# Becca_Sap_Flow_Power_Board_MOD.net
KiCad netlist of a schematic drawn in EAGLE
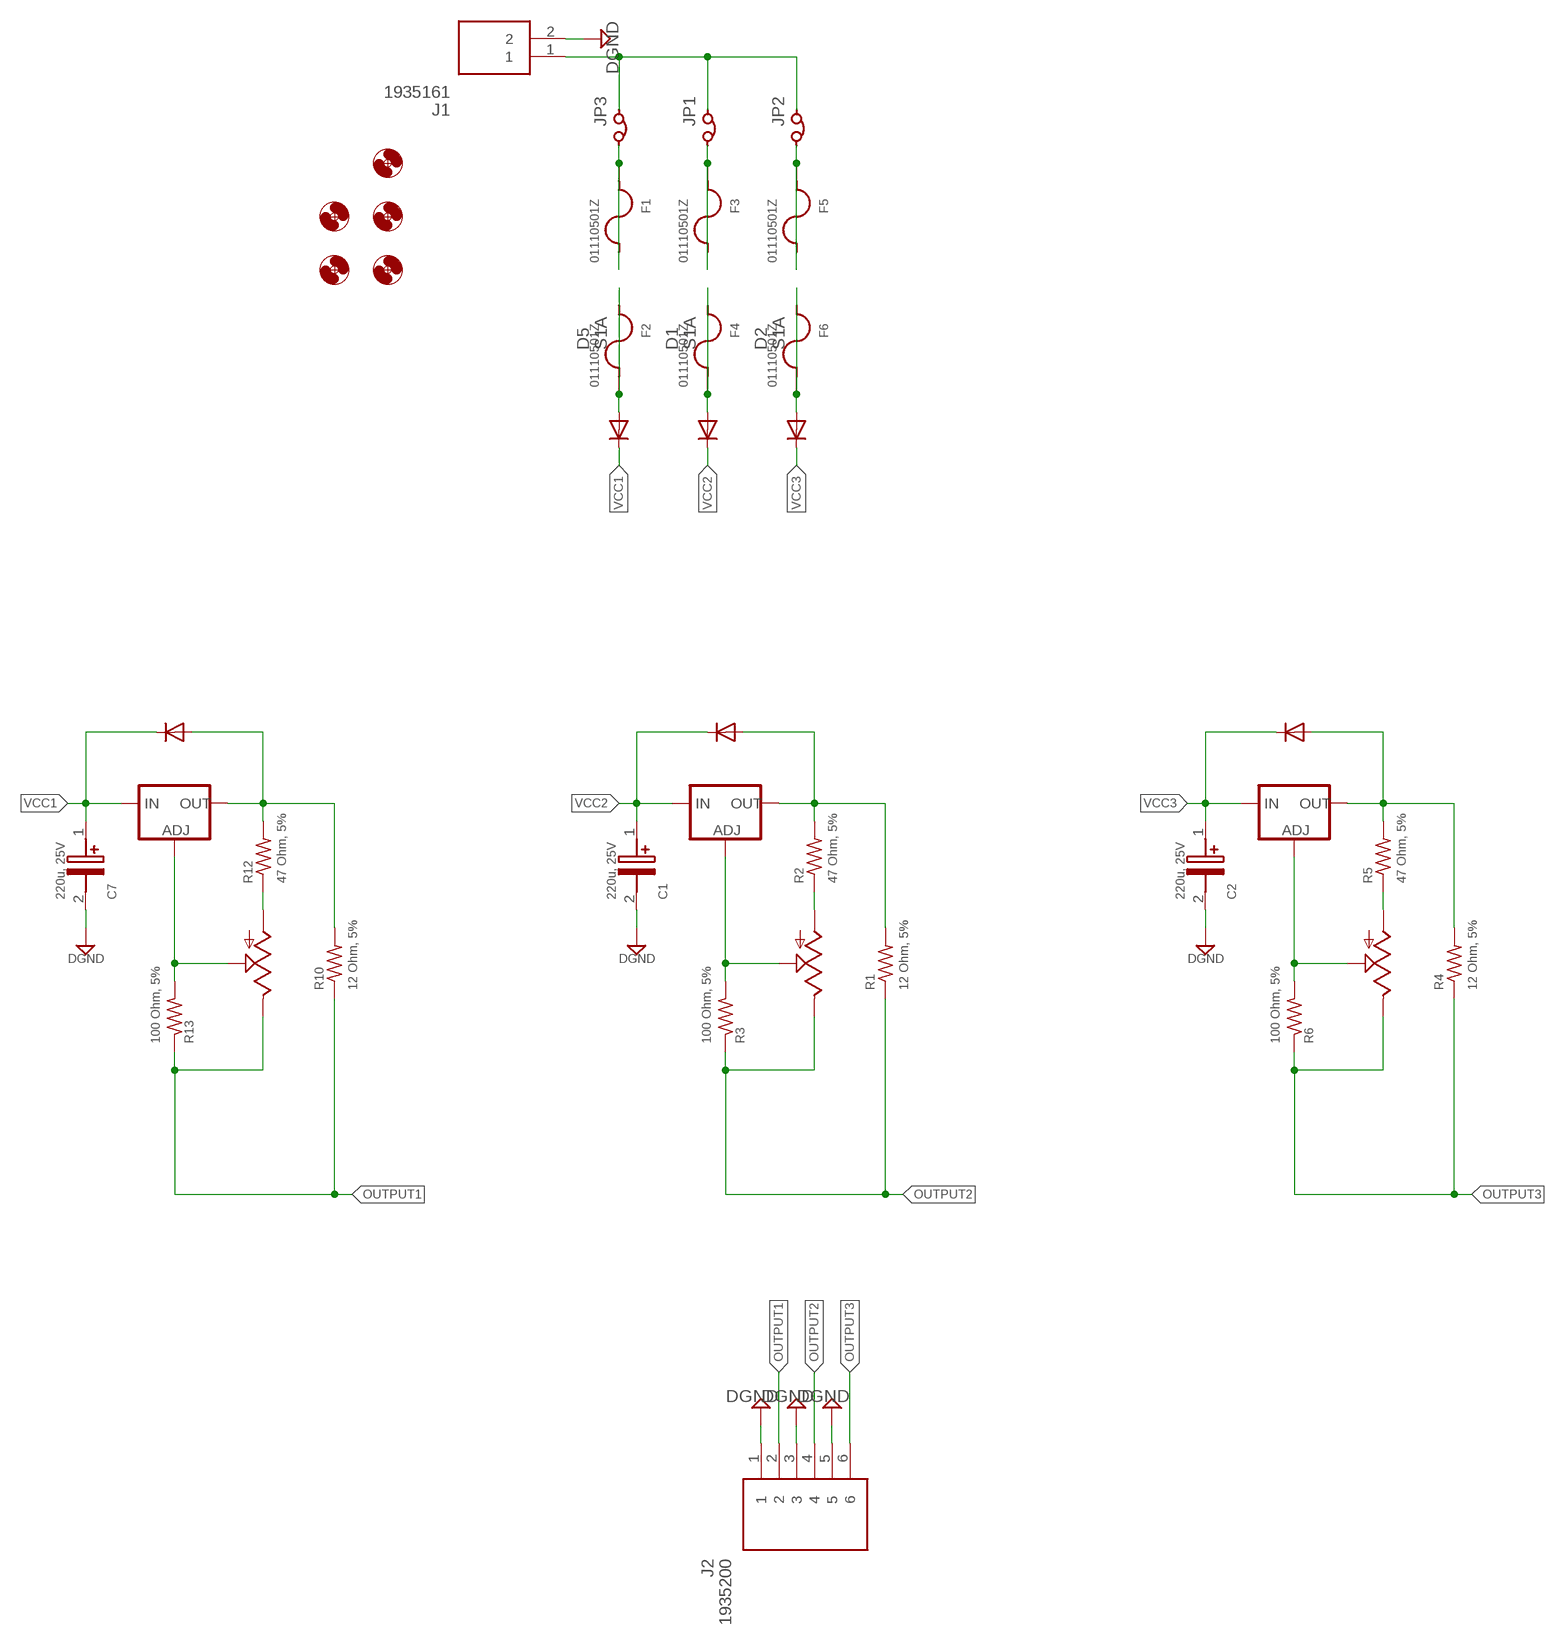
[diagram p0: schematic, sheet 1]

(export (version "E")
  (design (tool "Eeschema 10.0.6"))
  (components
    (comp (ref "C1")
      (value "220u, 25V")
      (footprint "eagle-import:CAPAE830X1080N")
      (fields
        (field (name "MANUFACTURER_PART_NUMBER") "UWT1E221MNL1GS")
        (field (name "MOUSER_PART_NUMBER") "647-UWT1E221MNL1GS")
      )
      (libsource (lib "eagle-import") (part "UWT1E221MNL1GS"))
    )
    (comp (ref "C2")
      (value "220u, 25V")
      (footprint "eagle-import:CAPAE830X1080N")
      (fields
        (field (name "MANUFACTURER_PART_NUMBER") "UWT1E221MNL1GS")
        (field (name "MOUSER_PART_NUMBER") "647-UWT1E221MNL1GS")
      )
      (libsource (lib "eagle-import") (part "UWT1E221MNL1GS"))
    )
    (comp (ref "C7")
      (value "220u, 25V")
      (footprint "eagle-import:CAPAE830X1080N")
      (fields
        (field (name "MANUFACTURER_PART_NUMBER") "UWT1E221MNL1GS")
        (field (name "MOUSER_PART_NUMBER") "647-UWT1E221MNL1GS")
      )
      (libsource (lib "eagle-import") (part "UWT1E221MNL1GS"))
    )
    (comp (ref "D1")
      (value "S1A")
      (footprint "eagle-import:DIOM5027X250N")
      (fields (field (name "MOUSER_PART_NUMBER") "637-S1A"))
      (libsource (lib "eagle-import") (part "S1A"))
    )
    (comp (ref "D2")
      (value "S1A")
      (footprint "eagle-import:DIOM5027X250N")
      (fields (field (name "MOUSER_PART_NUMBER") "637-S1A"))
      (libsource (lib "eagle-import") (part "S1A"))
    )
    (comp (ref "D3")
      (value "S1A")
      (footprint "eagle-import:DIOM5027X250N")
      (fields (field (name "MOUSER_PART_NUMBER") "637-S1A"))
      (libsource (lib "eagle-import") (part "S1A"))
    )
    (comp (ref "D4")
      (value "S1A")
      (footprint "eagle-import:DIOM5027X250N")
      (fields (field (name "MOUSER_PART_NUMBER") "637-S1A"))
      (libsource (lib "eagle-import") (part "S1A"))
    )
    (comp (ref "D5")
      (value "S1A")
      (footprint "eagle-import:DIOM5027X250N")
      (fields (field (name "MOUSER_PART_NUMBER") "637-S1A"))
      (libsource (lib "eagle-import") (part "S1A"))
    )
    (comp (ref "D6")
      (value "S1A")
      (footprint "eagle-import:DIOM5027X250N")
      (fields (field (name "MOUSER_PART_NUMBER") "637-S1A"))
      (libsource (lib "eagle-import") (part "S1A"))
    )
    (comp (ref "F1")
      (value "01110501Z")
      (footprint "eagle-import:01110501Z")
      (fields (field (name "MOUSER_PART_NUMBER") "576-01110501Z"))
      (libsource (lib "eagle-import") (part "01110501Z"))
    )
    (comp (ref "F2")
      (value "01110501Z")
      (footprint "eagle-import:01110501Z")
      (fields (field (name "MOUSER_PART_NUMBER") "576-01110501Z"))
      (libsource (lib "eagle-import") (part "01110501Z"))
    )
    (comp (ref "F3")
      (value "01110501Z")
      (footprint "eagle-import:01110501Z")
      (fields (field (name "MOUSER_PART_NUMBER") "576-01110501Z"))
      (libsource (lib "eagle-import") (part "01110501Z"))
    )
    (comp (ref "F4")
      (value "01110501Z")
      (footprint "eagle-import:01110501Z")
      (fields (field (name "MOUSER_PART_NUMBER") "576-01110501Z"))
      (libsource (lib "eagle-import") (part "01110501Z"))
    )
    (comp (ref "F5")
      (value "01110501Z")
      (footprint "eagle-import:01110501Z")
      (fields (field (name "MOUSER_PART_NUMBER") "576-01110501Z"))
      (libsource (lib "eagle-import") (part "01110501Z"))
    )
    (comp (ref "F6")
      (value "01110501Z")
      (footprint "eagle-import:01110501Z")
      (fields (field (name "MOUSER_PART_NUMBER") "576-01110501Z"))
      (libsource (lib "eagle-import") (part "01110501Z"))
    )
    (comp (ref "J1")
      (value "1935161")
      (footprint "eagle-import:1935161")
      (fields (field (name "MOUSER_PART_NUMBER") "651-1935161"))
      (libsource (lib "eagle-import") (part "1935161"))
    )
    (comp (ref "J2")
      (value "1935200")
      (footprint "eagle-import:1935200")
      (fields (field (name "MOUSER_PART_NUMBER") "651-1935200"))
      (libsource (lib "eagle-import") (part "1935200"))
    )
    (comp (ref "JP1")
      (value "JUMPER")
      (footprint "eagle-import:HDR2X1")
      (libsource (lib "eagle-import") (part "JUMPER"))
    )
    (comp (ref "JP2")
      (value "JUMPER")
      (footprint "eagle-import:HDR2X1")
      (libsource (lib "eagle-import") (part "JUMPER"))
    )
    (comp (ref "JP3")
      (value "JUMPER")
      (footprint "eagle-import:HDR2X1")
      (libsource (lib "eagle-import") (part "JUMPER"))
    )
    (comp (ref "R1")
      (value "12 Ohm, 5%")
      (footprint "eagle-import:R1210")
      (libsource (lib "eagle-import") (part "R-US_R1210"))
    )
    (comp (ref "R2")
      (value "47 Ohm, 5%")
      (footprint "eagle-import:R1210")
      (libsource (lib "eagle-import") (part "R-US_R1210"))
    )
    (comp (ref "R3")
      (value "100 Ohm, 5%")
      (footprint "eagle-import:R1210")
      (libsource (lib "eagle-import") (part "R-US_R1210"))
    )
    (comp (ref "R4")
      (value "12 Ohm, 5%")
      (footprint "eagle-import:R1210")
      (libsource (lib "eagle-import") (part "R-US_R1210"))
    )
    (comp (ref "R5")
      (value "47 Ohm, 5%")
      (footprint "eagle-import:R1210")
      (libsource (lib "eagle-import") (part "R-US_R1210"))
    )
    (comp (ref "R6")
      (value "100 Ohm, 5%")
      (footprint "eagle-import:R1210")
      (libsource (lib "eagle-import") (part "R-US_R1210"))
    )
    (comp (ref "R10")
      (value "12 Ohm, 5%")
      (footprint "eagle-import:R1210")
      (libsource (lib "eagle-import") (part "R-US_R1210"))
    )
    (comp (ref "R12")
      (value "47 Ohm, 5%")
      (footprint "eagle-import:R1210")
      (libsource (lib "eagle-import") (part "R-US_R1210"))
    )
    (comp (ref "R13")
      (value "100 Ohm, 5%")
      (footprint "eagle-import:R1210")
      (libsource (lib "eagle-import") (part "R-US_R1210"))
    )
    (comp (ref "U$1")
      (value "MOUNT-HOLE3.0")
      (footprint "eagle-import:3,0")
      (libsource (lib "eagle-import") (part "MOUNT-HOLE3.0"))
    )
    (comp (ref "U$2")
      (value "MOUNT-HOLE3.0")
      (footprint "eagle-import:3,0")
      (libsource (lib "eagle-import") (part "MOUNT-HOLE3.0"))
    )
    (comp (ref "U$3")
      (value "MOUNT-HOLE3.0")
      (footprint "eagle-import:3,0")
      (libsource (lib "eagle-import") (part "MOUNT-HOLE3.0"))
    )
    (comp (ref "U$4")
      (value "MOUNT-HOLE3.0")
      (footprint "eagle-import:3,0")
      (libsource (lib "eagle-import") (part "MOUNT-HOLE3.0"))
    )
    (comp (ref "U$5")
      (value "MOUNT-HOLE3.0")
      (footprint "eagle-import:3,0")
      (libsource (lib "eagle-import") (part "MOUNT-HOLE3.0"))
    )
    (comp (ref "U1")
      (value "LM317MBSTT3G")
      (footprint "eagle-import:SOT230P700X175-4N")
      (fields (field (name "MOUSER_PART_NUMBER") "863-LM317MBSTT3G"))
      (libsource (lib "eagle-import") (part "LM317MBSTT3G"))
    )
    (comp (ref "U2")
      (value "LM317MBSTT3G")
      (footprint "eagle-import:SOT230P700X175-4N")
      (fields (field (name "MOUSER_PART_NUMBER") "863-LM317MBSTT3G"))
      (libsource (lib "eagle-import") (part "LM317MBSTT3G"))
    )
    (comp (ref "U3")
      (value "LM317MBSTT3G")
      (footprint "eagle-import:SOT230P700X175-4N")
      (fields (field (name "MOUSER_PART_NUMBER") "863-LM317MBSTT3G"))
      (libsource (lib "eagle-import") (part "LM317MBSTT3G"))
    )
    (comp (ref "VR1")
      (value "3296W-1-102RLF")
      (footprint "eagle-import:3296W1102RLF")
      (fields (field (name "MOUSER_PART_NUMBER") "652-3296W-1-102RLF"))
      (libsource (lib "eagle-import") (part "3296W-1-102RLF"))
    )
    (comp (ref "VR2")
      (value "3296W-1-102RLF")
      (footprint "eagle-import:3296W1102RLF")
      (fields (field (name "MOUSER_PART_NUMBER") "652-3296W-1-102RLF"))
      (libsource (lib "eagle-import") (part "3296W-1-102RLF"))
    )
    (comp (ref "VR3")
      (value "3296W-1-102RLF")
      (footprint "eagle-import:3296W1102RLF")
      (fields (field (name "MOUSER_PART_NUMBER") "652-3296W-1-102RLF"))
      (libsource (lib "eagle-import") (part "3296W-1-102RLF"))
    )
  )
  (nets
    (net (code "1") (name "DGND") (class "Default")
      (node (ref "C1") (pin "2") (pinfunction "-_2") (pintype "bidirectional"))
      (node (ref "C2") (pin "2") (pinfunction "-_2") (pintype "bidirectional"))
      (node (ref "C7") (pin "2") (pinfunction "-_2") (pintype "bidirectional"))
      (node (ref "J1") (pin "2") (pinfunction "2_2") (pintype "bidirectional"))
      (node (ref "J2") (pin "1") (pinfunction "1_1") (pintype "bidirectional"))
      (node (ref "J2") (pin "3") (pinfunction "3_3") (pintype "bidirectional"))
      (node (ref "J2") (pin "5") (pinfunction "5_5") (pintype "bidirectional"))
    )
    (net (code "2") (name "Net-(D1-A)") (class "Default")
      (node (ref "D1") (pin "2") (pinfunction "A_2") (pintype "passive"))
      (node (ref "F4") (pin "1") (pinfunction "1_1") (pintype "passive"))
      (node (ref "F4") (pin "2") (pinfunction "2_2") (pintype "passive"))
    )
    (net (code "3") (name "Net-(D2-A)") (class "Default")
      (node (ref "D2") (pin "2") (pinfunction "A_2") (pintype "passive"))
      (node (ref "F6") (pin "1") (pinfunction "1_1") (pintype "passive"))
      (node (ref "F6") (pin "2") (pinfunction "2_2") (pintype "passive"))
    )
    (net (code "4") (name "Net-(D3-A)") (class "Default")
      (node (ref "D3") (pin "2") (pinfunction "A_2") (pintype "passive"))
      (node (ref "R1") (pin "2") (pinfunction "2_2") (pintype "passive"))
      (node (ref "R2") (pin "2") (pinfunction "2_2") (pintype "passive"))
      (node (ref "U2") (pin "2") (pinfunction "OUT_2") (pintype "output"))
    )
    (net (code "5") (name "Net-(D4-A)") (class "Default")
      (node (ref "D4") (pin "2") (pinfunction "A_2") (pintype "passive"))
      (node (ref "R4") (pin "2") (pinfunction "2_2") (pintype "passive"))
      (node (ref "R5") (pin "2") (pinfunction "2_2") (pintype "passive"))
      (node (ref "U3") (pin "2") (pinfunction "OUT_2") (pintype "output"))
    )
    (net (code "6") (name "Net-(D5-A)") (class "Default")
      (node (ref "D5") (pin "2") (pinfunction "A_2") (pintype "passive"))
      (node (ref "F2") (pin "1") (pinfunction "1_1") (pintype "passive"))
      (node (ref "F2") (pin "2") (pinfunction "2_2") (pintype "passive"))
    )
    (net (code "7") (name "Net-(D6-A)") (class "Default")
      (node (ref "D6") (pin "2") (pinfunction "A_2") (pintype "passive"))
      (node (ref "R10") (pin "2") (pinfunction "2_2") (pintype "passive"))
      (node (ref "R12") (pin "2") (pinfunction "2_2") (pintype "passive"))
      (node (ref "U1") (pin "2") (pinfunction "OUT_2") (pintype "output"))
    )
    (net (code "8") (name "Net-(F1-Pad1)") (class "Default")
      (node (ref "F1") (pin "1") (pinfunction "1_1") (pintype "passive"))
      (node (ref "F1") (pin "2") (pinfunction "2_2") (pintype "passive"))
      (node (ref "JP3") (pin "2") (pinfunction "2_2") (pintype "passive"))
    )
    (net (code "9") (name "Net-(F3-Pad1)") (class "Default")
      (node (ref "F3") (pin "1") (pinfunction "1_1") (pintype "passive"))
      (node (ref "F3") (pin "2") (pinfunction "2_2") (pintype "passive"))
      (node (ref "JP1") (pin "2") (pinfunction "2_2") (pintype "passive"))
    )
    (net (code "10") (name "Net-(F5-Pad1)") (class "Default")
      (node (ref "F5") (pin "1") (pinfunction "1_1") (pintype "passive"))
      (node (ref "F5") (pin "2") (pinfunction "2_2") (pintype "passive"))
      (node (ref "JP2") (pin "2") (pinfunction "2_2") (pintype "passive"))
    )
    (net (code "11") (name "Net-(J1-Pad1)") (class "Default")
      (node (ref "J1") (pin "1") (pinfunction "1_1") (pintype "bidirectional"))
      (node (ref "JP1") (pin "1") (pinfunction "1_1") (pintype "passive"))
      (node (ref "JP2") (pin "1") (pinfunction "1_1") (pintype "passive"))
      (node (ref "JP3") (pin "1") (pinfunction "1_1") (pintype "passive"))
    )
    (net (code "12") (name "Net-(U1-ADJ)") (class "Default")
      (node (ref "R13") (pin "2") (pinfunction "2_2") (pintype "passive"))
      (node (ref "U1") (pin "1") (pinfunction "ADJ_1") (pintype "input"))
      (node (ref "VR1") (pin "2") (pinfunction "S_2") (pintype "passive"))
    )
    (net (code "13") (name "Net-(U2-ADJ)") (class "Default")
      (node (ref "R3") (pin "2") (pinfunction "2_2") (pintype "passive"))
      (node (ref "U2") (pin "1") (pinfunction "ADJ_1") (pintype "input"))
      (node (ref "VR2") (pin "2") (pinfunction "S_2") (pintype "passive"))
    )
    (net (code "14") (name "Net-(U3-ADJ)") (class "Default")
      (node (ref "R6") (pin "2") (pinfunction "2_2") (pintype "passive"))
      (node (ref "U3") (pin "1") (pinfunction "ADJ_1") (pintype "input"))
      (node (ref "VR3") (pin "2") (pinfunction "S_2") (pintype "passive"))
    )
    (net (code "15") (name "Net-(VR1-A)") (class "Default")
      (node (ref "R12") (pin "1") (pinfunction "1_1") (pintype "passive"))
      (node (ref "VR1") (pin "1") (pinfunction "A_1") (pintype "passive"))
    )
    (net (code "16") (name "Net-(VR2-A)") (class "Default")
      (node (ref "R2") (pin "1") (pinfunction "1_1") (pintype "passive"))
      (node (ref "VR2") (pin "1") (pinfunction "A_1") (pintype "passive"))
    )
    (net (code "17") (name "Net-(VR3-A)") (class "Default")
      (node (ref "R5") (pin "1") (pinfunction "1_1") (pintype "passive"))
      (node (ref "VR3") (pin "1") (pinfunction "A_1") (pintype "passive"))
    )
    (net (code "18") (name "OUTPUT1") (class "Default")
      (node (ref "J2") (pin "2") (pinfunction "2_2") (pintype "bidirectional"))
      (node (ref "R10") (pin "1") (pinfunction "1_1") (pintype "passive"))
      (node (ref "R13") (pin "1") (pinfunction "1_1") (pintype "passive"))
      (node (ref "VR1") (pin "3") (pinfunction "E_3") (pintype "passive"))
    )
    (net (code "19") (name "OUTPUT2") (class "Default")
      (node (ref "J2") (pin "4") (pinfunction "4_4") (pintype "bidirectional"))
      (node (ref "R1") (pin "1") (pinfunction "1_1") (pintype "passive"))
      (node (ref "R3") (pin "1") (pinfunction "1_1") (pintype "passive"))
      (node (ref "VR2") (pin "3") (pinfunction "E_3") (pintype "passive"))
    )
    (net (code "20") (name "OUTPUT3") (class "Default")
      (node (ref "J2") (pin "6") (pinfunction "6_6") (pintype "bidirectional"))
      (node (ref "R4") (pin "1") (pinfunction "1_1") (pintype "passive"))
      (node (ref "R6") (pin "1") (pinfunction "1_1") (pintype "passive"))
      (node (ref "VR3") (pin "3") (pinfunction "E_3") (pintype "passive"))
    )
    (net (code "21") (name "VCC1") (class "Default")
      (node (ref "C7") (pin "1") (pinfunction "+_1") (pintype "bidirectional"))
      (node (ref "D5") (pin "1") (pinfunction "K_1") (pintype "passive"))
      (node (ref "D6") (pin "1") (pinfunction "K_1") (pintype "passive"))
      (node (ref "U1") (pin "3") (pinfunction "IN_3") (pintype "input"))
    )
    (net (code "22") (name "VCC2") (class "Default")
      (node (ref "C1") (pin "1") (pinfunction "+_1") (pintype "bidirectional"))
      (node (ref "D1") (pin "1") (pinfunction "K_1") (pintype "passive"))
      (node (ref "D3") (pin "1") (pinfunction "K_1") (pintype "passive"))
      (node (ref "U2") (pin "3") (pinfunction "IN_3") (pintype "input"))
    )
    (net (code "23") (name "VCC3") (class "Default")
      (node (ref "C2") (pin "1") (pinfunction "+_1") (pintype "bidirectional"))
      (node (ref "D2") (pin "1") (pinfunction "K_1") (pintype "passive"))
      (node (ref "D4") (pin "1") (pinfunction "K_1") (pintype "passive"))
      (node (ref "U3") (pin "3") (pinfunction "IN_3") (pintype "input"))
    )
  )
)
